# amp_test_3.net
KiCad netlist of a schematic drawn in EAGLE
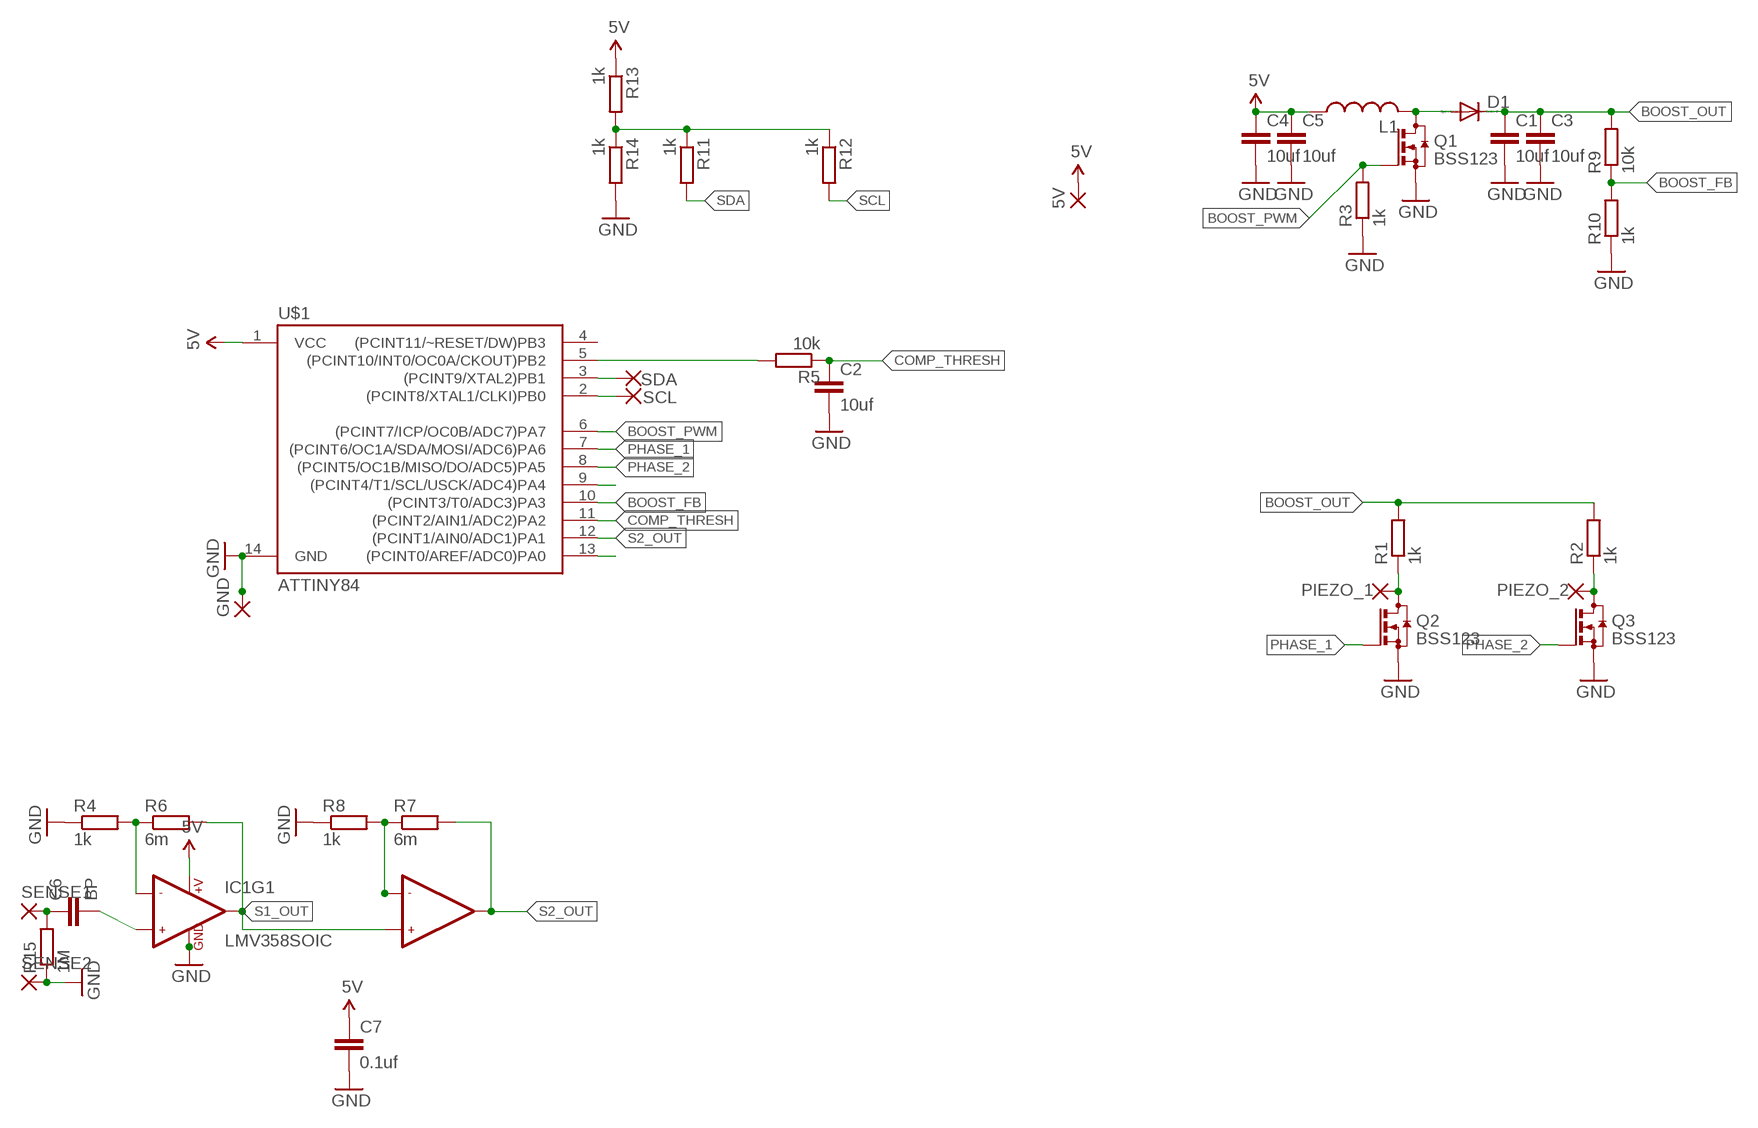
[diagram p0: schematic, sheet 1]

(export (version "E")
  (design (tool "Eeschema 10.0.6"))
  (components
    (comp (ref "5V")
      (value "SMD5")
      (footprint "eagle-import:SMD2,54-5,08")
      (libsource (lib "eagle-import") (part "SMD5"))
    )
    (comp (ref "C1")
      (value "10uf")
      (footprint "eagle-import:C0603")
      (libsource (lib "eagle-import") (part "C-EUC0603"))
    )
    (comp (ref "C2")
      (value "10uf")
      (footprint "eagle-import:C0603")
      (libsource (lib "eagle-import") (part "C-EUC0603"))
    )
    (comp (ref "C3")
      (value "10uf")
      (footprint "eagle-import:C0603")
      (libsource (lib "eagle-import") (part "C-EUC0603"))
    )
    (comp (ref "C4")
      (value "10uf")
      (footprint "eagle-import:C0603")
      (libsource (lib "eagle-import") (part "C-EUC0603"))
    )
    (comp (ref "C5")
      (value "10uf")
      (footprint "eagle-import:C0603")
      (libsource (lib "eagle-import") (part "C-EUC0603"))
    )
    (comp (ref "C6")
      (value "BP")
      (footprint "eagle-import:C0603")
      (libsource (lib "eagle-import") (part "C-EUC0603"))
    )
    (comp (ref "C7")
      (value "0.1uf")
      (footprint "eagle-import:C0603")
      (libsource (lib "eagle-import") (part "C-EUC0603"))
    )
    (comp (ref "D1")
      (value "CGRM4001-G")
      (footprint "eagle-import:SOD-123_MINI-SMA")
      (libsource (lib "eagle-import") (part "CGRM400-G1"))
    )
    (comp (ref "GND")
      (value "SMD5")
      (footprint "eagle-import:SMD2,54-5,08")
      (libsource (lib "eagle-import") (part "SMD5"))
    )
    (comp (ref "IC1")
      (value "LMV358SOIC")
      (footprint "eagle-import:SO08")
      (libsource (lib "eagle-import") (part "LMV358SOIC"))
    )
    (comp (ref "L1")
      (value "L-USL2825P")
      (footprint "eagle-import:L2825P")
      (libsource (lib "eagle-import") (part "L-USL2825P"))
    )
    (comp (ref "PIEZO_1")
      (value "SMD5")
      (footprint "eagle-import:SMD2,54-5,08")
      (libsource (lib "eagle-import") (part "SMD5"))
    )
    (comp (ref "PIEZO_2")
      (value "SMD5")
      (footprint "eagle-import:SMD2,54-5,08")
      (libsource (lib "eagle-import") (part "SMD5"))
    )
    (comp (ref "Q1")
      (value "BSS123")
      (footprint "eagle-import:SOT23")
      (libsource (lib "eagle-import") (part "BSS123"))
    )
    (comp (ref "Q2")
      (value "BSS123")
      (footprint "eagle-import:SOT23")
      (libsource (lib "eagle-import") (part "BSS123"))
    )
    (comp (ref "Q3")
      (value "BSS123")
      (footprint "eagle-import:SOT23")
      (libsource (lib "eagle-import") (part "BSS123"))
    )
    (comp (ref "R1")
      (value "1k")
      (footprint "eagle-import:R0603")
      (libsource (lib "eagle-import") (part "R-EU_R0603"))
    )
    (comp (ref "R2")
      (value "1k")
      (footprint "eagle-import:R0603")
      (libsource (lib "eagle-import") (part "R-EU_R0603"))
    )
    (comp (ref "R3")
      (value "1k")
      (footprint "eagle-import:R0603")
      (libsource (lib "eagle-import") (part "R-EU_R0603"))
    )
    (comp (ref "R4")
      (value "1k")
      (footprint "eagle-import:R0603")
      (libsource (lib "eagle-import") (part "R-EU_R0603"))
    )
    (comp (ref "R5")
      (value "10k")
      (footprint "eagle-import:R0603")
      (libsource (lib "eagle-import") (part "R-EU_R0603"))
    )
    (comp (ref "R6")
      (value "6m")
      (footprint "eagle-import:R0603")
      (libsource (lib "eagle-import") (part "R-EU_R0603"))
    )
    (comp (ref "R7")
      (value "6m")
      (footprint "eagle-import:R0603")
      (libsource (lib "eagle-import") (part "R-EU_R0603"))
    )
    (comp (ref "R8")
      (value "1k")
      (footprint "eagle-import:R0603")
      (libsource (lib "eagle-import") (part "R-EU_R0603"))
    )
    (comp (ref "R9")
      (value "10k")
      (footprint "eagle-import:R0603")
      (libsource (lib "eagle-import") (part "R-EU_R0603"))
    )
    (comp (ref "R10")
      (value "1k")
      (footprint "eagle-import:R0603")
      (libsource (lib "eagle-import") (part "R-EU_R0603"))
    )
    (comp (ref "R11")
      (value "1k")
      (footprint "eagle-import:R0603")
      (libsource (lib "eagle-import") (part "R-EU_R0603"))
    )
    (comp (ref "R12")
      (value "1k")
      (footprint "eagle-import:R0603")
      (libsource (lib "eagle-import") (part "R-EU_R0603"))
    )
    (comp (ref "R13")
      (value "1k")
      (footprint "eagle-import:R0603")
      (libsource (lib "eagle-import") (part "R-EU_R0603"))
    )
    (comp (ref "R14")
      (value "1k")
      (footprint "eagle-import:R0603")
      (libsource (lib "eagle-import") (part "R-EU_R0603"))
    )
    (comp (ref "R15")
      (value "1M")
      (footprint "eagle-import:R0603")
      (libsource (lib "eagle-import") (part "R-EU_R0603"))
    )
    (comp (ref "SCL")
      (value "SMD5")
      (footprint "eagle-import:SMD2,54-5,08")
      (libsource (lib "eagle-import") (part "SMD5"))
    )
    (comp (ref "SDA")
      (value "SMD5")
      (footprint "eagle-import:SMD2,54-5,08")
      (libsource (lib "eagle-import") (part "SMD5"))
    )
    (comp (ref "SENSE1")
      (value "SMD5")
      (footprint "eagle-import:SMD2,54-5,08")
      (libsource (lib "eagle-import") (part "SMD5"))
    )
    (comp (ref "SENSE2")
      (value "SMD5")
      (footprint "eagle-import:SMD2,54-5,08")
      (libsource (lib "eagle-import") (part "SMD5"))
    )
    (comp (ref "U$1")
      (value "ATTINY84")
      (footprint "eagle-import:SO14")
      (libsource (lib "eagle-import") (part "ATTINY84"))
    )
  )
  (nets
    (net (code "1") (name "5V") (class "Default")
      (node (ref "5V") (pin "1") (pinfunction "P_1") (pintype "passive"))
      (node (ref "C4") (pin "1") (pinfunction "1_1") (pintype "passive"))
      (node (ref "C5") (pin "1") (pinfunction "1_1") (pintype "passive"))
      (node (ref "C7") (pin "1") (pinfunction "1_1") (pintype "passive"))
      (node (ref "IC1") (pin "8") (pinfunction "+V_8") (pintype "power_in"))
      (node (ref "L1") (pin "1") (pinfunction "1_1") (pintype "passive"))
      (node (ref "R13") (pin "1") (pinfunction "1_1") (pintype "passive"))
      (node (ref "U$1") (pin "1") (pinfunction "VCC_1") (pintype "bidirectional"))
    )
    (net (code "2") (name "BOOST_FB") (class "Default")
      (node (ref "R10") (pin "2") (pinfunction "2_2") (pintype "passive"))
      (node (ref "R9") (pin "1") (pinfunction "1_1") (pintype "passive"))
      (node (ref "U$1") (pin "10") (pinfunction "(PCINT3/T0/ADC3)PA3_10") (pintype "bidirectional"))
    )
    (net (code "3") (name "BOOST_OUT") (class "Default")
      (node (ref "C1") (pin "1") (pinfunction "1_1") (pintype "passive"))
      (node (ref "C3") (pin "1") (pinfunction "1_1") (pintype "passive"))
      (node (ref "D1") (pin "C") (pinfunction "C_C") (pintype "passive"))
      (node (ref "R1") (pin "2") (pinfunction "2_2") (pintype "passive"))
      (node (ref "R2") (pin "2") (pinfunction "2_2") (pintype "passive"))
      (node (ref "R9") (pin "2") (pinfunction "2_2") (pintype "passive"))
    )
    (net (code "4") (name "BOOST_PWM") (class "Default")
      (node (ref "Q1") (pin "1") (pinfunction "G_1") (pintype "passive"))
      (node (ref "R3") (pin "2") (pinfunction "2_2") (pintype "passive"))
      (node (ref "U$1") (pin "6") (pinfunction "(PCINT7/ICP/OC0B/ADC7)PA7_6") (pintype "bidirectional"))
    )
    (net (code "5") (name "COMP_THRESH") (class "Default")
      (node (ref "C2") (pin "1") (pinfunction "1_1") (pintype "passive"))
      (node (ref "R5") (pin "1") (pinfunction "1_1") (pintype "passive"))
      (node (ref "U$1") (pin "11") (pinfunction "(PCINT2/AIN1/ADC2)PA2_11") (pintype "bidirectional"))
    )
    (net (code "6") (name "GND") (class "Default")
      (node (ref "C1") (pin "2") (pinfunction "2_2") (pintype "passive"))
      (node (ref "C2") (pin "2") (pinfunction "2_2") (pintype "passive"))
      (node (ref "C3") (pin "2") (pinfunction "2_2") (pintype "passive"))
      (node (ref "C4") (pin "2") (pinfunction "2_2") (pintype "passive"))
      (node (ref "C5") (pin "2") (pinfunction "2_2") (pintype "passive"))
      (node (ref "C7") (pin "2") (pinfunction "2_2") (pintype "passive"))
      (node (ref "GND") (pin "1") (pinfunction "P_1") (pintype "passive"))
      (node (ref "IC1") (pin "4") (pinfunction "GND_4") (pintype "power_in"))
      (node (ref "Q1") (pin "2") (pinfunction "S_2") (pintype "passive"))
      (node (ref "Q2") (pin "2") (pinfunction "S_2") (pintype "passive"))
      (node (ref "Q3") (pin "2") (pinfunction "S_2") (pintype "passive"))
      (node (ref "R10") (pin "1") (pinfunction "1_1") (pintype "passive"))
      (node (ref "R14") (pin "2") (pinfunction "2_2") (pintype "passive"))
      (node (ref "R15") (pin "1") (pinfunction "1_1") (pintype "passive"))
      (node (ref "R3") (pin "1") (pinfunction "1_1") (pintype "passive"))
      (node (ref "R4") (pin "1") (pinfunction "1_1") (pintype "passive"))
      (node (ref "R8") (pin "1") (pinfunction "1_1") (pintype "passive"))
      (node (ref "SENSE2") (pin "1") (pinfunction "P_1") (pintype "passive"))
      (node (ref "U$1") (pin "14") (pinfunction "GND_14") (pintype "bidirectional"))
    )
    (net (code "7") (name "Net-(IC1A-+IN1)") (class "Default")
      (node (ref "C6") (pin "2") (pinfunction "2_2") (pintype "passive"))
      (node (ref "IC1") (pin "3") (pinfunction "+IN1_3") (pintype "input"))
    )
    (net (code "8") (name "Net-(IC1A--IN1)") (class "Default")
      (node (ref "IC1") (pin "2") (pinfunction "-IN1_2") (pintype "input"))
      (node (ref "R4") (pin "2") (pinfunction "2_2") (pintype "passive"))
      (node (ref "R6") (pin "1") (pinfunction "1_1") (pintype "passive"))
    )
    (net (code "9") (name "Net-(IC1B--IN2)") (class "Default")
      (node (ref "IC1") (pin "6") (pinfunction "-IN2_6") (pintype "input"))
      (node (ref "R7") (pin "1") (pinfunction "1_1") (pintype "passive"))
      (node (ref "R8") (pin "2") (pinfunction "2_2") (pintype "passive"))
    )
    (net (code "10") (name "Net-(PIEZO_1-P)") (class "Default")
      (node (ref "PIEZO_1") (pin "1") (pinfunction "P_1") (pintype "passive"))
      (node (ref "Q2") (pin "3") (pinfunction "D_3") (pintype "passive"))
      (node (ref "R1") (pin "1") (pinfunction "1_1") (pintype "passive"))
    )
    (net (code "11") (name "Net-(PIEZO_2-P)") (class "Default")
      (node (ref "PIEZO_2") (pin "1") (pinfunction "P_1") (pintype "passive"))
      (node (ref "Q3") (pin "3") (pinfunction "D_3") (pintype "passive"))
      (node (ref "R2") (pin "1") (pinfunction "1_1") (pintype "passive"))
    )
    (net (code "12") (name "Net-(Q1-D)") (class "Default")
      (node (ref "D1") (pin "A") (pinfunction "A_A") (pintype "passive"))
      (node (ref "L1") (pin "2") (pinfunction "2_2") (pintype "passive"))
      (node (ref "Q1") (pin "3") (pinfunction "D_3") (pintype "passive"))
    )
    (net (code "13") (name "Net-(R11-Pad1)") (class "Default")
      (node (ref "R11") (pin "1") (pinfunction "1_1") (pintype "passive"))
      (node (ref "R12") (pin "1") (pinfunction "1_1") (pintype "passive"))
      (node (ref "R13") (pin "2") (pinfunction "2_2") (pintype "passive"))
      (node (ref "R14") (pin "1") (pinfunction "1_1") (pintype "passive"))
    )
    (net (code "14") (name "Net-(SENSE1-P)") (class "Default")
      (node (ref "C6") (pin "1") (pinfunction "1_1") (pintype "passive"))
      (node (ref "R15") (pin "2") (pinfunction "2_2") (pintype "passive"))
      (node (ref "SENSE1") (pin "1") (pinfunction "P_1") (pintype "passive"))
    )
    (net (code "15") (name "Net-(U$1-(PCINT10{slash}INT0{slash}OC0A{slash}CKOUT)PB2)") (class "Default")
      (node (ref "R5") (pin "2") (pinfunction "2_2") (pintype "passive"))
      (node (ref "U$1") (pin "5") (pinfunction "(PCINT10/INT0/OC0A/CKOUT)PB2_5") (pintype "bidirectional"))
    )
    (net (code "16") (name "PHASE_1") (class "Default")
      (node (ref "Q2") (pin "1") (pinfunction "G_1") (pintype "passive"))
      (node (ref "U$1") (pin "7") (pinfunction "(PCINT6/OC1A/SDA/MOSI/ADC6)PA6_7") (pintype "bidirectional"))
    )
    (net (code "17") (name "PHASE_2") (class "Default")
      (node (ref "Q3") (pin "1") (pinfunction "G_1") (pintype "passive"))
      (node (ref "U$1") (pin "8") (pinfunction "(PCINT5/OC1B/MISO/DO/ADC5)PA5_8") (pintype "bidirectional"))
    )
    (net (code "18") (name "S1_OUT") (class "Default")
      (node (ref "IC1") (pin "1") (pinfunction "OUT1_1") (pintype "output"))
      (node (ref "IC1") (pin "5") (pinfunction "+IN2_5") (pintype "input"))
      (node (ref "R6") (pin "2") (pinfunction "2_2") (pintype "passive"))
    )
    (net (code "19") (name "S2_OUT") (class "Default")
      (node (ref "IC1") (pin "7") (pinfunction "OUT2_7") (pintype "output"))
      (node (ref "R7") (pin "2") (pinfunction "2_2") (pintype "passive"))
      (node (ref "U$1") (pin "12") (pinfunction "(PCINT1/AIN0/ADC1)PA1_12") (pintype "bidirectional"))
    )
    (net (code "20") (name "SCL") (class "Default")
      (node (ref "R12") (pin "2") (pinfunction "2_2") (pintype "passive"))
      (node (ref "SCL") (pin "1") (pinfunction "P_1") (pintype "passive"))
      (node (ref "U$1") (pin "2") (pinfunction "(PCINT8/XTAL1/CLKI)PB0_2") (pintype "bidirectional"))
    )
    (net (code "21") (name "SDA") (class "Default")
      (node (ref "R11") (pin "2") (pinfunction "2_2") (pintype "passive"))
      (node (ref "SDA") (pin "1") (pinfunction "P_1") (pintype "passive"))
      (node (ref "U$1") (pin "3") (pinfunction "(PCINT9/XTAL2)PB1_3") (pintype "bidirectional"))
    )
    (net (code "22") (name "unconnected-(U$1-(PCINT0{slash}AREF{slash}ADC0)PA0-Pad13)") (class "Default")
      (node (ref "U$1") (pin "13") (pinfunction "(PCINT0/AREF/ADC0)PA0_13") (pintype "bidirectional"))
    )
    (net (code "23") (name "unconnected-(U$1-(PCINT4{slash}T1{slash}SCL{slash}USCK{slash}ADC4)PA4-Pad9)") (class "Default")
      (node (ref "U$1") (pin "9") (pinfunction "(PCINT4/T1/SCL/USCK/ADC4)PA4_9") (pintype "bidirectional"))
    )
    (net (code "24") (name "unconnected-(U$1-(PCINT11{slash}~{RESET{slash}DW})PB3-Pad4)") (class "Default")
      (node (ref "U$1") (pin "4") (pinfunction "(PCINT11/~{RESET/DW})PB3_4") (pintype "bidirectional"))
    )
  )
)
